# 8266_DIYIOT_Board_J_AS_G_V_DS.net
KiCad netlist of a schematic drawn in EAGLE
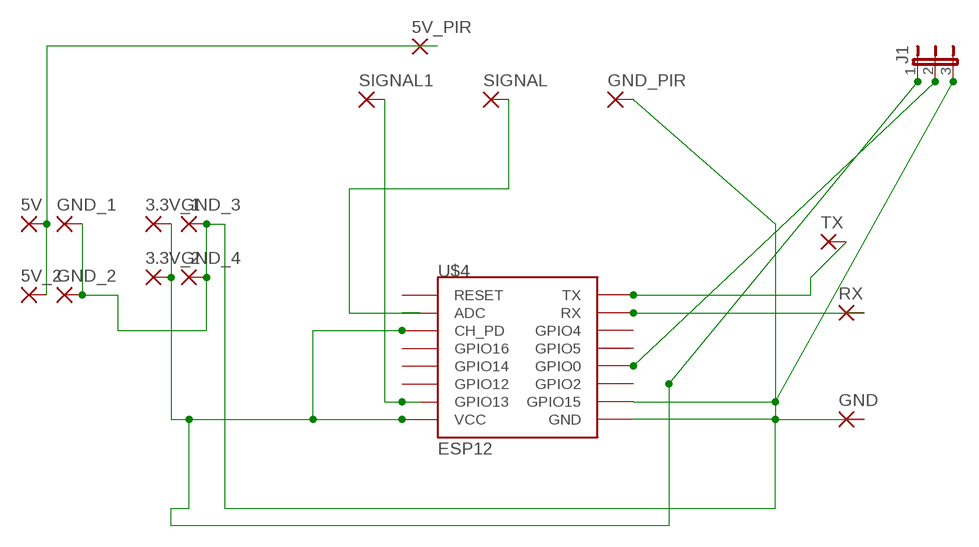
[diagram p0: schematic, sheet 1]

(export (version "E")
  (design (tool "Eeschema 10.0.6"))
  (components
    (comp (ref "3.3V_1")
      (value "2,15/1,0")
      (footprint "eagle-import:2,15_1,0")
      (libsource (lib "eagle-import") (part "2,15/1,0"))
    )
    (comp (ref "3.3V_2")
      (value "2,15/1,0")
      (footprint "eagle-import:2,15_1,0")
      (libsource (lib "eagle-import") (part "2,15/1,0"))
    )
    (comp (ref "5V")
      (value "2,15/1,0")
      (footprint "eagle-import:2,15_1,0")
      (libsource (lib "eagle-import") (part "2,15/1,0"))
    )
    (comp (ref "5V_2")
      (value "2,15/1,0")
      (footprint "eagle-import:2,15_1,0")
      (libsource (lib "eagle-import") (part "2,15/1,0"))
    )
    (comp (ref "5V_PIR")
      (value "2,15/1,0")
      (footprint "eagle-import:2,15_1,0")
      (libsource (lib "eagle-import") (part "2,15/1,0"))
    )
    (comp (ref "GND")
      (value "2,15/1,0")
      (footprint "eagle-import:2,15_1,0")
      (libsource (lib "eagle-import") (part "2,15/1,0"))
    )
    (comp (ref "GND_1")
      (value "2,15/1,0")
      (footprint "eagle-import:2,15_1,0")
      (libsource (lib "eagle-import") (part "2,15/1,0"))
    )
    (comp (ref "GND_2")
      (value "2,15/1,0")
      (footprint "eagle-import:2,15_1,0")
      (libsource (lib "eagle-import") (part "2,15/1,0"))
    )
    (comp (ref "GND_3")
      (value "2,15/1,0")
      (footprint "eagle-import:2,15_1,0")
      (libsource (lib "eagle-import") (part "2,15/1,0"))
    )
    (comp (ref "GND_4")
      (value "2,15/1,0")
      (footprint "eagle-import:2,15_1,0")
      (libsource (lib "eagle-import") (part "2,15/1,0"))
    )
    (comp (ref "GND_PIR")
      (value "2,15/1,0")
      (footprint "eagle-import:2,15_1,0")
      (libsource (lib "eagle-import") (part "2,15/1,0"))
    )
    (comp (ref "J1")
      (value "JP2E")
      (footprint "eagle-import:JP2")
      (libsource (lib "eagle-import") (part "JP2E"))
    )
    (comp (ref "RX")
      (value "2,15/1,0")
      (footprint "eagle-import:2,15_1,0")
      (libsource (lib "eagle-import") (part "2,15/1,0"))
    )
    (comp (ref "SIGNAL")
      (value "2,15/1,0")
      (footprint "eagle-import:2,15_1,0")
      (libsource (lib "eagle-import") (part "2,15/1,0"))
    )
    (comp (ref "SIGNAL1")
      (value "2,15/1,0")
      (footprint "eagle-import:2,15_1,0")
      (libsource (lib "eagle-import") (part "2,15/1,0"))
    )
    (comp (ref "TX")
      (value "2,15/1,0")
      (footprint "eagle-import:2,15_1,0")
      (libsource (lib "eagle-import") (part "2,15/1,0"))
    )
    (comp (ref "U$4")
      (value "ESP12")
      (footprint "eagle-import:ESP12")
      (libsource (lib "eagle-import") (part "ESP12"))
    )
  )
  (nets
    (net (code "1") (name "/5V") (class "Default")
      (node (ref "5V") (pin "1") (pinfunction "P_1") (pintype "passive"))
      (node (ref "5V_2") (pin "1") (pinfunction "P_1") (pintype "passive"))
      (node (ref "5V_PIR") (pin "1") (pinfunction "P_1") (pintype "passive"))
      (node (ref "GND") (pin "1") (pinfunction "P_1") (pintype "passive"))
      (node (ref "GND_1") (pin "1") (pinfunction "P_1") (pintype "passive"))
      (node (ref "GND_2") (pin "1") (pinfunction "P_1") (pintype "passive"))
      (node (ref "GND_3") (pin "1") (pinfunction "P_1") (pintype "passive"))
      (node (ref "GND_4") (pin "1") (pinfunction "P_1") (pintype "passive"))
      (node (ref "GND_PIR") (pin "1") (pinfunction "P_1") (pintype "passive"))
      (node (ref "J1") (pin "3") (pinfunction "3_3") (pintype "passive"))
      (node (ref "U$4") (pin "GND") (pinfunction "GND_GND") (pintype "bidirectional"))
      (node (ref "U$4") (pin "GPIO15") (pinfunction "GPIO15_GPIO15") (pintype "bidirectional"))
    )
    (net (code "2") (name "Net-(3.3V_1-P)") (class "Default")
      (node (ref "3.3V_1") (pin "1") (pinfunction "P_1") (pintype "passive"))
      (node (ref "3.3V_2") (pin "1") (pinfunction "P_1") (pintype "passive"))
      (node (ref "J1") (pin "1") (pinfunction "1_1") (pintype "passive"))
      (node (ref "U$4") (pin "CH_PD") (pinfunction "CH_PD_CH_PD") (pintype "bidirectional"))
      (node (ref "U$4") (pin "VCC") (pinfunction "VCC_VCC") (pintype "bidirectional"))
    )
    (net (code "3") (name "Net-(J1-Pad2)") (class "Default")
      (node (ref "J1") (pin "2") (pinfunction "2_2") (pintype "passive"))
      (node (ref "U$4") (pin "GPIO0") (pinfunction "GPIO0_GPIO0") (pintype "bidirectional"))
    )
    (net (code "4") (name "Net-(RX-P)") (class "Default")
      (node (ref "RX") (pin "1") (pinfunction "P_1") (pintype "passive"))
      (node (ref "U$4") (pin "RX") (pinfunction "RX_RX") (pintype "bidirectional"))
    )
    (net (code "5") (name "Net-(SIGNAL-P)") (class "Default")
      (node (ref "SIGNAL") (pin "1") (pinfunction "P_1") (pintype "passive"))
      (node (ref "U$4") (pin "ADC") (pinfunction "ADC_ADC") (pintype "bidirectional"))
    )
    (net (code "6") (name "Net-(SIGNAL1-P)") (class "Default")
      (node (ref "SIGNAL1") (pin "1") (pinfunction "P_1") (pintype "passive"))
      (node (ref "U$4") (pin "GPIO13") (pinfunction "GPIO13_GPIO13") (pintype "bidirectional"))
    )
    (net (code "7") (name "Net-(TX-P)") (class "Default")
      (node (ref "TX") (pin "1") (pinfunction "P_1") (pintype "passive"))
      (node (ref "U$4") (pin "TX") (pinfunction "TX_TX") (pintype "bidirectional"))
    )
    (net (code "8") (name "unconnected-(U$4-PadGPIO2)") (class "Default")
      (node (ref "U$4") (pin "GPIO2") (pinfunction "GPIO2_GPIO2") (pintype "bidirectional"))
    )
    (net (code "9") (name "unconnected-(U$4-PadGPIO4)") (class "Default")
      (node (ref "U$4") (pin "GPIO4") (pinfunction "GPIO4_GPIO4") (pintype "bidirectional"))
    )
    (net (code "10") (name "unconnected-(U$4-PadGPIO5)") (class "Default")
      (node (ref "U$4") (pin "GPIO5") (pinfunction "GPIO5_GPIO5") (pintype "bidirectional"))
    )
    (net (code "11") (name "unconnected-(U$4-PadGPIO12)") (class "Default")
      (node (ref "U$4") (pin "GPIO12") (pinfunction "GPIO12_GPIO12") (pintype "bidirectional"))
    )
    (net (code "12") (name "unconnected-(U$4-PadGPIO14)") (class "Default")
      (node (ref "U$4") (pin "GPIO14") (pinfunction "GPIO14_GPIO14") (pintype "bidirectional"))
    )
    (net (code "13") (name "unconnected-(U$4-PadGPIO16)") (class "Default")
      (node (ref "U$4") (pin "GPIO16") (pinfunction "GPIO16_GPIO16") (pintype "bidirectional"))
    )
    (net (code "14") (name "unconnected-(U$4-PadRESET)") (class "Default")
      (node (ref "U$4") (pin "RESET") (pinfunction "RESET_RESET") (pintype "bidirectional"))
    )
  )
)
